# TNY-NROM-02.net
KiCad netlist of a schematic drawn in EAGLE
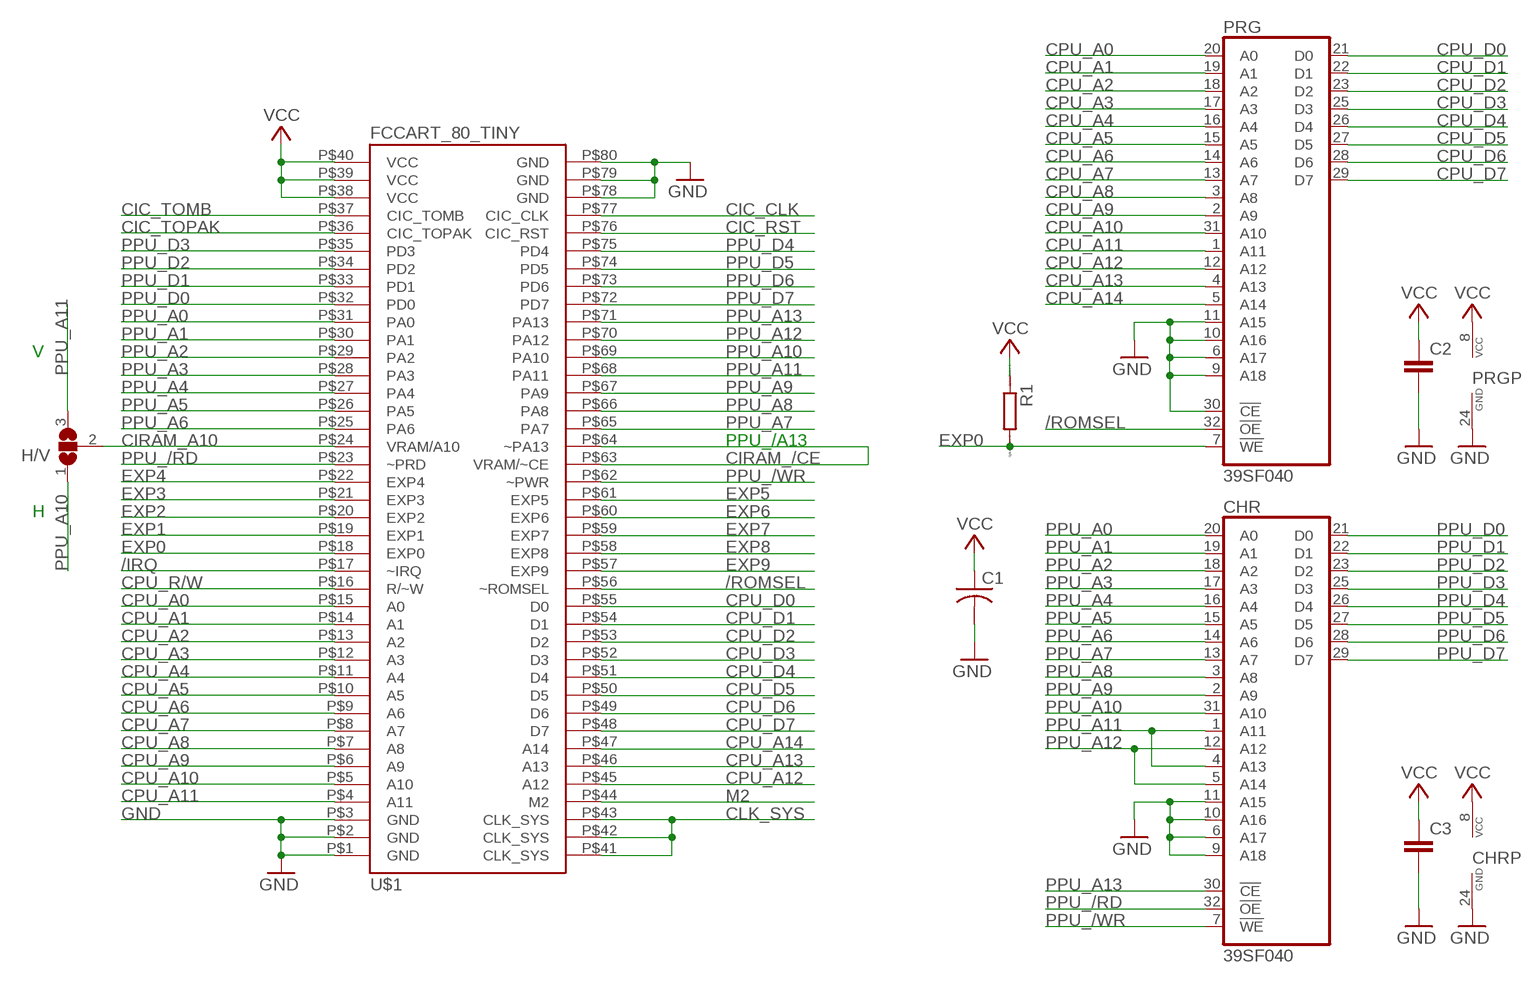
[diagram p0: schematic, sheet 1]

(export (version "E")
  (design (tool "Eeschema 10.0.6"))
  (components
    (comp (ref "C1")
      (value "C-USC1206")
      (footprint "eagle-import:C1206")
      (libsource (lib "eagle-import") (part "C-USC1206"))
    )
    (comp (ref "C2")
      (value "C-EUC0603K")
      (footprint "eagle-import:C0603K")
      (libsource (lib "eagle-import") (part "C-EUC0603K"))
    )
    (comp (ref "C3")
      (value "C-EUC0603K")
      (footprint "eagle-import:C0603K")
      (libsource (lib "eagle-import") (part "C-EUC0603K"))
    )
    (comp (ref "CHR")
      (value "39SF040")
      (footprint "eagle-import:TSOP32_SHORT")
      (libsource (lib "eagle-import") (part "AM29F040ESHORT"))
    )
    (comp (ref "H/V")
      (value "SJ2W")
      (footprint "eagle-import:SJ_2")
      (libsource (lib "eagle-import") (part "SJ2W"))
    )
    (comp (ref "PRG")
      (value "39SF040")
      (footprint "eagle-import:TSOP32_SHORT")
      (libsource (lib "eagle-import") (part "AM29F040ESHORT"))
    )
    (comp (ref "R1")
      (value "RR0603")
      (footprint "eagle-import:R0603")
      (libsource (lib "eagle-import") (part "RR0603"))
    )
    (comp (ref "U$1")
      (value "FCCART_80_TINY")
      (footprint "eagle-import:FCCART_80_TINY")
      (libsource (lib "eagle-import") (part "FCCART_80_TINY"))
    )
  )
  (nets
    (net (code "1") (name "/CIC_CLK") (class "Default")
      (node (ref "U$1") (pin "P$77") (pinfunction "CIC_CLK_P$77") (pintype "bidirectional"))
    )
    (net (code "2") (name "/CIC_RST") (class "Default")
      (node (ref "U$1") (pin "P$76") (pinfunction "CIC_RST_P$76") (pintype "bidirectional"))
    )
    (net (code "3") (name "/CIC_TOMB") (class "Default")
      (node (ref "U$1") (pin "P$37") (pinfunction "CIC_TOMB_P$37") (pintype "bidirectional"))
    )
    (net (code "4") (name "/CIC_TOPAK") (class "Default")
      (node (ref "U$1") (pin "P$36") (pinfunction "CIC_TOPAK_P$36") (pintype "bidirectional"))
    )
    (net (code "5") (name "/CIRAM_A10") (class "Default")
      (node (ref "H/V") (pin "2") (pinfunction "2_2") (pintype "passive"))
      (node (ref "U$1") (pin "P$24") (pinfunction "VRAM/A10_P$24") (pintype "input"))
    )
    (net (code "6") (name "/CIRAM_{slash}CE") (class "Default")
      (node (ref "U$1") (pin "P$63") (pinfunction "VRAM/~{CE}_P$63") (pintype "input"))
      (node (ref "U$1") (pin "P$64") (pinfunction "~{PA13}_P$64") (pintype "output"))
    )
    (net (code "7") (name "/CLK_SYS") (class "Default")
      (node (ref "U$1") (pin "P$41") (pinfunction "CLK_SYS_P$41") (pintype "power_in"))
      (node (ref "U$1") (pin "P$42") (pinfunction "CLK_SYS_P$42") (pintype "power_in"))
      (node (ref "U$1") (pin "P$43") (pinfunction "CLK_SYS_P$43") (pintype "power_in"))
    )
    (net (code "8") (name "/CPU_A0") (class "Default")
      (node (ref "PRG") (pin "20") (pinfunction "A0_20") (pintype "input"))
      (node (ref "U$1") (pin "P$15") (pinfunction "A0_P$15") (pintype "output"))
    )
    (net (code "9") (name "/CPU_A1") (class "Default")
      (node (ref "PRG") (pin "19") (pinfunction "A1_19") (pintype "input"))
      (node (ref "U$1") (pin "P$14") (pinfunction "A1_P$14") (pintype "output"))
    )
    (net (code "10") (name "/CPU_A2") (class "Default")
      (node (ref "PRG") (pin "18") (pinfunction "A2_18") (pintype "input"))
      (node (ref "U$1") (pin "P$13") (pinfunction "A2_P$13") (pintype "output"))
    )
    (net (code "11") (name "/CPU_A3") (class "Default")
      (node (ref "PRG") (pin "17") (pinfunction "A3_17") (pintype "input"))
      (node (ref "U$1") (pin "P$12") (pinfunction "A3_P$12") (pintype "output"))
    )
    (net (code "12") (name "/CPU_A4") (class "Default")
      (node (ref "PRG") (pin "16") (pinfunction "A4_16") (pintype "input"))
      (node (ref "U$1") (pin "P$11") (pinfunction "A4_P$11") (pintype "output"))
    )
    (net (code "13") (name "/CPU_A5") (class "Default")
      (node (ref "PRG") (pin "15") (pinfunction "A5_15") (pintype "input"))
      (node (ref "U$1") (pin "P$10") (pinfunction "A5_P$10") (pintype "output"))
    )
    (net (code "14") (name "/CPU_A6") (class "Default")
      (node (ref "PRG") (pin "14") (pinfunction "A6_14") (pintype "input"))
      (node (ref "U$1") (pin "P$9") (pinfunction "A6_P$9") (pintype "output"))
    )
    (net (code "15") (name "/CPU_A7") (class "Default")
      (node (ref "PRG") (pin "13") (pinfunction "A7_13") (pintype "input"))
      (node (ref "U$1") (pin "P$8") (pinfunction "A7_P$8") (pintype "output"))
    )
    (net (code "16") (name "/CPU_A8") (class "Default")
      (node (ref "PRG") (pin "3") (pinfunction "A8_3") (pintype "input"))
      (node (ref "U$1") (pin "P$7") (pinfunction "A8_P$7") (pintype "output"))
    )
    (net (code "17") (name "/CPU_A9") (class "Default")
      (node (ref "PRG") (pin "2") (pinfunction "A9_2") (pintype "input"))
      (node (ref "U$1") (pin "P$6") (pinfunction "A9_P$6") (pintype "output"))
    )
    (net (code "18") (name "/CPU_A10") (class "Default")
      (node (ref "PRG") (pin "31") (pinfunction "A10_31") (pintype "input"))
      (node (ref "U$1") (pin "P$5") (pinfunction "A10_P$5") (pintype "output"))
    )
    (net (code "19") (name "/CPU_A11") (class "Default")
      (node (ref "PRG") (pin "1") (pinfunction "A11_1") (pintype "input"))
      (node (ref "U$1") (pin "P$4") (pinfunction "A11_P$4") (pintype "output"))
    )
    (net (code "20") (name "/CPU_A12") (class "Default")
      (node (ref "PRG") (pin "12") (pinfunction "A12_12") (pintype "input"))
      (node (ref "U$1") (pin "P$45") (pinfunction "A12_P$45") (pintype "output"))
    )
    (net (code "21") (name "/CPU_A13") (class "Default")
      (node (ref "PRG") (pin "4") (pinfunction "A13_4") (pintype "input"))
      (node (ref "U$1") (pin "P$46") (pinfunction "A13_P$46") (pintype "output"))
    )
    (net (code "22") (name "/CPU_A14") (class "Default")
      (node (ref "PRG") (pin "5") (pinfunction "A14_5") (pintype "input"))
      (node (ref "U$1") (pin "P$47") (pinfunction "A14_P$47") (pintype "output"))
    )
    (net (code "23") (name "/CPU_D0") (class "Default")
      (node (ref "PRG") (pin "21") (pinfunction "D0_21") (pintype "tri_state"))
      (node (ref "U$1") (pin "P$55") (pinfunction "D0_P$55") (pintype "output"))
    )
    (net (code "24") (name "/CPU_D1") (class "Default")
      (node (ref "PRG") (pin "22") (pinfunction "D1_22") (pintype "tri_state"))
      (node (ref "U$1") (pin "P$54") (pinfunction "D1_P$54") (pintype "output"))
    )
    (net (code "25") (name "/CPU_D2") (class "Default")
      (node (ref "PRG") (pin "23") (pinfunction "D2_23") (pintype "tri_state"))
      (node (ref "U$1") (pin "P$53") (pinfunction "D2_P$53") (pintype "output"))
    )
    (net (code "26") (name "/CPU_D3") (class "Default")
      (node (ref "PRG") (pin "25") (pinfunction "D3_25") (pintype "tri_state"))
      (node (ref "U$1") (pin "P$52") (pinfunction "D3_P$52") (pintype "output"))
    )
    (net (code "27") (name "/CPU_D4") (class "Default")
      (node (ref "PRG") (pin "26") (pinfunction "D4_26") (pintype "tri_state"))
      (node (ref "U$1") (pin "P$51") (pinfunction "D4_P$51") (pintype "output"))
    )
    (net (code "28") (name "/CPU_D5") (class "Default")
      (node (ref "PRG") (pin "27") (pinfunction "D5_27") (pintype "tri_state"))
      (node (ref "U$1") (pin "P$50") (pinfunction "D5_P$50") (pintype "output"))
    )
    (net (code "29") (name "/CPU_D6") (class "Default")
      (node (ref "PRG") (pin "28") (pinfunction "D6_28") (pintype "tri_state"))
      (node (ref "U$1") (pin "P$49") (pinfunction "D6_P$49") (pintype "output"))
    )
    (net (code "30") (name "/CPU_D7") (class "Default")
      (node (ref "PRG") (pin "29") (pinfunction "D7_29") (pintype "tri_state"))
      (node (ref "U$1") (pin "P$48") (pinfunction "D7_P$48") (pintype "output"))
    )
    (net (code "31") (name "/CPU_R{slash}W") (class "Default")
      (node (ref "U$1") (pin "P$16") (pinfunction "R/~{W}_P$16") (pintype "output"))
    )
    (net (code "32") (name "/EXP0") (class "Default")
      (node (ref "PRG") (pin "7") (pinfunction "~{WE}_7") (pintype "input"))
      (node (ref "R1") (pin "2") (pinfunction "2_2") (pintype "passive"))
      (node (ref "U$1") (pin "P$18") (pinfunction "EXP0_P$18") (pintype "power_in"))
    )
    (net (code "33") (name "/EXP1") (class "Default")
      (node (ref "U$1") (pin "P$19") (pinfunction "EXP1_P$19") (pintype "power_in"))
    )
    (net (code "34") (name "/EXP2") (class "Default")
      (node (ref "U$1") (pin "P$20") (pinfunction "EXP2_P$20") (pintype "power_in"))
    )
    (net (code "35") (name "/EXP3") (class "Default")
      (node (ref "U$1") (pin "P$21") (pinfunction "EXP3_P$21") (pintype "power_in"))
    )
    (net (code "36") (name "/EXP4") (class "Default")
      (node (ref "U$1") (pin "P$22") (pinfunction "EXP4_P$22") (pintype "power_in"))
    )
    (net (code "37") (name "/EXP5") (class "Default")
      (node (ref "U$1") (pin "P$61") (pinfunction "EXP5_P$61") (pintype "input"))
    )
    (net (code "38") (name "/EXP6") (class "Default")
      (node (ref "U$1") (pin "P$60") (pinfunction "EXP6_P$60") (pintype "output"))
    )
    (net (code "39") (name "/EXP7") (class "Default")
      (node (ref "U$1") (pin "P$59") (pinfunction "EXP7_P$59") (pintype "power_in"))
    )
    (net (code "40") (name "/EXP8") (class "Default")
      (node (ref "U$1") (pin "P$58") (pinfunction "EXP8_P$58") (pintype "power_in"))
    )
    (net (code "41") (name "/EXP9") (class "Default")
      (node (ref "U$1") (pin "P$57") (pinfunction "EXP9_P$57") (pintype "power_in"))
    )
    (net (code "42") (name "/M2") (class "Default")
      (node (ref "U$1") (pin "P$44") (pinfunction "M2_P$44") (pintype "output"))
    )
    (net (code "43") (name "/PPU_A0") (class "Default")
      (node (ref "CHR") (pin "20") (pinfunction "A0_20") (pintype "input"))
      (node (ref "U$1") (pin "P$31") (pinfunction "PA0_P$31") (pintype "output"))
    )
    (net (code "44") (name "/PPU_A1") (class "Default")
      (node (ref "CHR") (pin "19") (pinfunction "A1_19") (pintype "input"))
      (node (ref "U$1") (pin "P$30") (pinfunction "PA1_P$30") (pintype "output"))
    )
    (net (code "45") (name "/PPU_A2") (class "Default")
      (node (ref "CHR") (pin "18") (pinfunction "A2_18") (pintype "input"))
      (node (ref "U$1") (pin "P$29") (pinfunction "PA2_P$29") (pintype "output"))
    )
    (net (code "46") (name "/PPU_A3") (class "Default")
      (node (ref "CHR") (pin "17") (pinfunction "A3_17") (pintype "input"))
      (node (ref "U$1") (pin "P$28") (pinfunction "PA3_P$28") (pintype "output"))
    )
    (net (code "47") (name "/PPU_A4") (class "Default")
      (node (ref "CHR") (pin "16") (pinfunction "A4_16") (pintype "input"))
      (node (ref "U$1") (pin "P$27") (pinfunction "PA4_P$27") (pintype "output"))
    )
    (net (code "48") (name "/PPU_A5") (class "Default")
      (node (ref "CHR") (pin "15") (pinfunction "A5_15") (pintype "input"))
      (node (ref "U$1") (pin "P$26") (pinfunction "PA5_P$26") (pintype "output"))
    )
    (net (code "49") (name "/PPU_A6") (class "Default")
      (node (ref "CHR") (pin "14") (pinfunction "A6_14") (pintype "input"))
      (node (ref "U$1") (pin "P$25") (pinfunction "PA6_P$25") (pintype "output"))
    )
    (net (code "50") (name "/PPU_A7") (class "Default")
      (node (ref "CHR") (pin "13") (pinfunction "A7_13") (pintype "input"))
      (node (ref "U$1") (pin "P$65") (pinfunction "PA7_P$65") (pintype "output"))
    )
    (net (code "51") (name "/PPU_A8") (class "Default")
      (node (ref "CHR") (pin "3") (pinfunction "A8_3") (pintype "input"))
      (node (ref "U$1") (pin "P$66") (pinfunction "PA8_P$66") (pintype "output"))
    )
    (net (code "52") (name "/PPU_A9") (class "Default")
      (node (ref "CHR") (pin "2") (pinfunction "A9_2") (pintype "input"))
      (node (ref "U$1") (pin "P$67") (pinfunction "PA9_P$67") (pintype "output"))
    )
    (net (code "53") (name "/PPU_A10") (class "Default")
      (node (ref "CHR") (pin "31") (pinfunction "A10_31") (pintype "input"))
      (node (ref "H/V") (pin "1") (pinfunction "1_1") (pintype "passive"))
      (node (ref "U$1") (pin "P$69") (pinfunction "PA10_P$69") (pintype "output"))
    )
    (net (code "54") (name "/PPU_A11") (class "Default")
      (node (ref "CHR") (pin "1") (pinfunction "A11_1") (pintype "input"))
      (node (ref "CHR") (pin "4") (pinfunction "A13_4") (pintype "input"))
      (node (ref "H/V") (pin "3") (pinfunction "3_3") (pintype "passive"))
      (node (ref "U$1") (pin "P$68") (pinfunction "PA11_P$68") (pintype "output"))
    )
    (net (code "55") (name "/PPU_A12") (class "Default")
      (node (ref "CHR") (pin "12") (pinfunction "A12_12") (pintype "input"))
      (node (ref "CHR") (pin "5") (pinfunction "A14_5") (pintype "input"))
      (node (ref "U$1") (pin "P$70") (pinfunction "PA12_P$70") (pintype "output"))
    )
    (net (code "56") (name "/PPU_A13") (class "Default")
      (node (ref "CHR") (pin "30") (pinfunction "~{CE}_30") (pintype "input"))
      (node (ref "U$1") (pin "P$71") (pinfunction "PA13_P$71") (pintype "output"))
    )
    (net (code "57") (name "/PPU_D0") (class "Default")
      (node (ref "CHR") (pin "21") (pinfunction "D0_21") (pintype "tri_state"))
      (node (ref "U$1") (pin "P$32") (pinfunction "PD0_P$32") (pintype "bidirectional"))
    )
    (net (code "58") (name "/PPU_D1") (class "Default")
      (node (ref "CHR") (pin "22") (pinfunction "D1_22") (pintype "tri_state"))
      (node (ref "U$1") (pin "P$33") (pinfunction "PD1_P$33") (pintype "bidirectional"))
    )
    (net (code "59") (name "/PPU_D2") (class "Default")
      (node (ref "CHR") (pin "23") (pinfunction "D2_23") (pintype "tri_state"))
      (node (ref "U$1") (pin "P$34") (pinfunction "PD2_P$34") (pintype "bidirectional"))
    )
    (net (code "60") (name "/PPU_D3") (class "Default")
      (node (ref "CHR") (pin "25") (pinfunction "D3_25") (pintype "tri_state"))
      (node (ref "U$1") (pin "P$35") (pinfunction "PD3_P$35") (pintype "bidirectional"))
    )
    (net (code "61") (name "/PPU_D4") (class "Default")
      (node (ref "CHR") (pin "26") (pinfunction "D4_26") (pintype "tri_state"))
      (node (ref "U$1") (pin "P$75") (pinfunction "PD4_P$75") (pintype "bidirectional"))
    )
    (net (code "62") (name "/PPU_D5") (class "Default")
      (node (ref "CHR") (pin "27") (pinfunction "D5_27") (pintype "tri_state"))
      (node (ref "U$1") (pin "P$74") (pinfunction "PD5_P$74") (pintype "bidirectional"))
    )
    (net (code "63") (name "/PPU_D6") (class "Default")
      (node (ref "CHR") (pin "28") (pinfunction "D6_28") (pintype "tri_state"))
      (node (ref "U$1") (pin "P$73") (pinfunction "PD6_P$73") (pintype "bidirectional"))
    )
    (net (code "64") (name "/PPU_D7") (class "Default")
      (node (ref "CHR") (pin "29") (pinfunction "D7_29") (pintype "tri_state"))
      (node (ref "U$1") (pin "P$72") (pinfunction "PD7_P$72") (pintype "bidirectional"))
    )
    (net (code "65") (name "/PPU_{slash}RD") (class "Default")
      (node (ref "CHR") (pin "32") (pinfunction "~{OE}_32") (pintype "input"))
      (node (ref "U$1") (pin "P$23") (pinfunction "~{PRD}_P$23") (pintype "output"))
    )
    (net (code "66") (name "/PPU_{slash}WR") (class "Default")
      (node (ref "CHR") (pin "7") (pinfunction "~{WE}_7") (pintype "input"))
      (node (ref "U$1") (pin "P$62") (pinfunction "~{PWR}_P$62") (pintype "output"))
    )
    (net (code "67") (name "/{slash}IRQ") (class "Default")
      (node (ref "U$1") (pin "P$17") (pinfunction "~{IRQ}_P$17") (pintype "output"))
    )
    (net (code "68") (name "/{slash}ROMSEL") (class "Default")
      (node (ref "PRG") (pin "32") (pinfunction "~{OE}_32") (pintype "input"))
      (node (ref "U$1") (pin "P$56") (pinfunction "~{ROMSEL}_P$56") (pintype "output"))
    )
    (net (code "69") (name "GND") (class "Default")
      (node (ref "C1") (pin "2") (pinfunction "2_2") (pintype "passive"))
      (node (ref "C2") (pin "2") (pinfunction "2_2") (pintype "passive"))
      (node (ref "C3") (pin "2") (pinfunction "2_2") (pintype "passive"))
      (node (ref "CHR") (pin "10") (pinfunction "A16_10") (pintype "input"))
      (node (ref "CHR") (pin "11") (pinfunction "A15_11") (pintype "input"))
      (node (ref "CHR") (pin "24") (pinfunction "GND_24") (pintype "power_in"))
      (node (ref "CHR") (pin "6") (pinfunction "A17_6") (pintype "input"))
      (node (ref "CHR") (pin "9") (pinfunction "A18_9") (pintype "input"))
      (node (ref "PRG") (pin "10") (pinfunction "A16_10") (pintype "input"))
      (node (ref "PRG") (pin "11") (pinfunction "A15_11") (pintype "input"))
      (node (ref "PRG") (pin "24") (pinfunction "GND_24") (pintype "power_in"))
      (node (ref "PRG") (pin "30") (pinfunction "~{CE}_30") (pintype "input"))
      (node (ref "PRG") (pin "6") (pinfunction "A17_6") (pintype "input"))
      (node (ref "PRG") (pin "9") (pinfunction "A18_9") (pintype "input"))
      (node (ref "U$1") (pin "P$1") (pinfunction "GND_P$1") (pintype "power_in"))
      (node (ref "U$1") (pin "P$2") (pinfunction "GND_P$2") (pintype "power_in"))
      (node (ref "U$1") (pin "P$3") (pinfunction "GND_P$3") (pintype "power_in"))
      (node (ref "U$1") (pin "P$78") (pinfunction "GND_P$78") (pintype "power_in"))
      (node (ref "U$1") (pin "P$79") (pinfunction "GND_P$79") (pintype "power_in"))
      (node (ref "U$1") (pin "P$80") (pinfunction "GND_P$80") (pintype "power_in"))
    )
    (net (code "70") (name "VCC") (class "Default")
      (node (ref "C1") (pin "1") (pinfunction "1_1") (pintype "passive"))
      (node (ref "C2") (pin "1") (pinfunction "1_1") (pintype "passive"))
      (node (ref "C3") (pin "1") (pinfunction "1_1") (pintype "passive"))
      (node (ref "CHR") (pin "8") (pinfunction "VCC_8") (pintype "power_in"))
      (node (ref "PRG") (pin "8") (pinfunction "VCC_8") (pintype "power_in"))
      (node (ref "R1") (pin "1") (pinfunction "1_1") (pintype "passive"))
      (node (ref "U$1") (pin "P$38") (pinfunction "VCC_P$38") (pintype "power_in"))
      (node (ref "U$1") (pin "P$39") (pinfunction "VCC_P$39") (pintype "power_in"))
      (node (ref "U$1") (pin "P$40") (pinfunction "VCC_P$40") (pintype "power_in"))
    )
  )
)
